# 1pcb.net
KiCad netlist of a schematic drawn in EAGLE
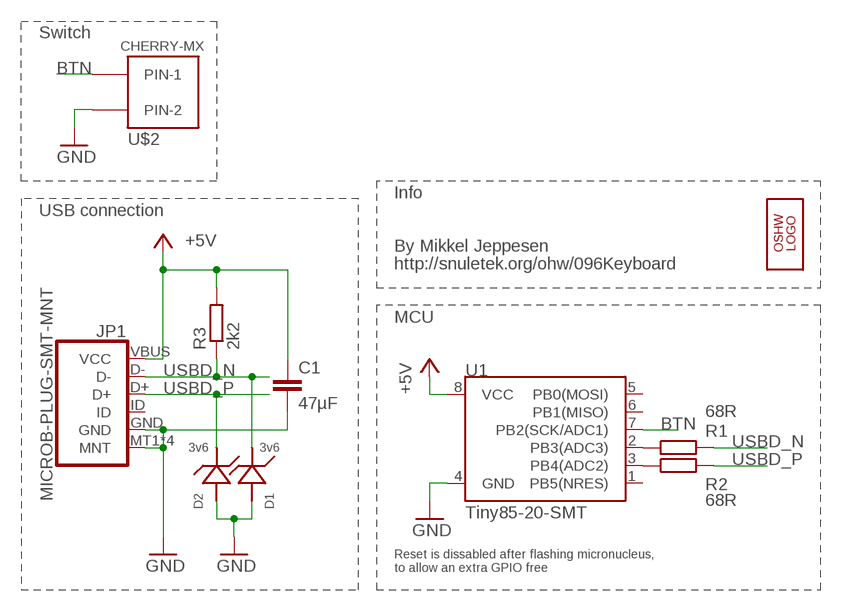
[diagram p0: schematic, sheet 1]

(export (version "E")
  (design (tool "Eeschema 10.0.6"))
  (components
    (comp (ref "C1")
      (value "47µF")
      (footprint "eagle-import:C3216")
      (libsource (lib "eagle-import") (part "C-EUC3216"))
    )
    (comp (ref "D1")
      (value "3v6")
      (footprint "eagle-import:SOD-523")
      (libsource (lib "eagle-import") (part "ZENER-DIODE"))
    )
    (comp (ref "D2")
      (value "3v6")
      (footprint "eagle-import:SOD-523")
      (libsource (lib "eagle-import") (part "ZENER-DIODE"))
    )
    (comp (ref "JP1")
      (value "MICROB-PLUG-SMT-MNT")
      (footprint "eagle-import:USB-MICROB")
      (libsource (lib "eagle-import") (part "MICROB-PLUG-SMT-MNT"))
    )
    (comp (ref "LOGO1")
      (value "OSHW_LOGO_6MILX0070-NT")
      (footprint "eagle-import:OSHW_6X70_NOTEXT")
      (libsource (lib "eagle-import") (part "OSHW_LOGO_6MILX0070-NT"))
    )
    (comp (ref "R1")
      (value "68R")
      (footprint "eagle-import:R0603")
      (libsource (lib "eagle-import") (part "R-EU_R0603"))
    )
    (comp (ref "R2")
      (value "68R")
      (footprint "eagle-import:R0603")
      (libsource (lib "eagle-import") (part "R-EU_R0603"))
    )
    (comp (ref "R3")
      (value "2k2")
      (footprint "eagle-import:R0603")
      (libsource (lib "eagle-import") (part "R-EU_R0603"))
    )
    (comp (ref "U$2")
      (value "CHERRY-MX-I")
      (footprint "eagle-import:CHERRY-MX-I")
      (libsource (lib "eagle-import") (part "CHERRY-MX-I"))
    )
    (comp (ref "U1")
      (value "Tiny85-20-SMT")
      (footprint "eagle-import:SO08-EIAJ")
      (libsource (lib "eagle-import") (part "ATTINY45TINY85-20-SMT"))
    )
  )
  (nets
    (net (code "1") (name "+5V") (class "Default")
      (node (ref "C1") (pin "1") (pinfunction "1_1") (pintype "passive"))
      (node (ref "JP1") (pin "VBUS") (pinfunction "VCC_VBUS") (pintype "bidirectional"))
      (node (ref "R3") (pin "2") (pinfunction "2_2") (pintype "passive"))
      (node (ref "U1") (pin "8") (pinfunction "VCC_8") (pintype "bidirectional"))
    )
    (net (code "2") (name "/BTN") (class "Default")
      (node (ref "U$2") (pin "PIN-1") (pinfunction "PIN-1_PIN-1") (pintype "bidirectional"))
      (node (ref "U1") (pin "7") (pinfunction "PB2(SCK/ADC1)_7") (pintype "bidirectional"))
    )
    (net (code "3") (name "/USBD_N") (class "Default")
      (node (ref "D1") (pin "C") (pinfunction "C_C") (pintype "bidirectional"))
      (node (ref "JP1") (pin "D-") (pinfunction "D-_D-") (pintype "bidirectional"))
      (node (ref "R1") (pin "2") (pinfunction "2_2") (pintype "passive"))
      (node (ref "R3") (pin "1") (pinfunction "1_1") (pintype "passive"))
    )
    (net (code "4") (name "/USBD_P") (class "Default")
      (node (ref "D2") (pin "C") (pinfunction "C_C") (pintype "bidirectional"))
      (node (ref "JP1") (pin "D+") (pinfunction "D+_D+") (pintype "bidirectional"))
      (node (ref "R2") (pin "2") (pinfunction "2_2") (pintype "passive"))
    )
    (net (code "5") (name "GND") (class "Default")
      (node (ref "C1") (pin "2") (pinfunction "2_2") (pintype "passive"))
      (node (ref "D1") (pin "A") (pinfunction "A_A") (pintype "bidirectional"))
      (node (ref "D2") (pin "A") (pinfunction "A_A") (pintype "bidirectional"))
      (node (ref "JP1") (pin "GND") (pinfunction "GND_GND") (pintype "bidirectional"))
      (node (ref "JP1") (pin "MT1") (pinfunction "MNT_MT1") (pintype "bidirectional"))
      (node (ref "JP1") (pin "MT2") (pinfunction "MNT_MT2") (pintype "bidirectional"))
      (node (ref "JP1") (pin "P$1") (pinfunction "MNT_P$1") (pintype "bidirectional"))
      (node (ref "JP1") (pin "P$2") (pinfunction "MNT_P$2") (pintype "bidirectional"))
      (node (ref "U$2") (pin "PIN-2") (pinfunction "PIN-2_PIN-2") (pintype "bidirectional"))
      (node (ref "U1") (pin "4") (pinfunction "GND_4") (pintype "bidirectional"))
    )
    (net (code "6") (name "Net-(U1-PB3(ADC3))") (class "Default")
      (node (ref "R1") (pin "1") (pinfunction "1_1") (pintype "passive"))
      (node (ref "U1") (pin "2") (pinfunction "PB3(ADC3)_2") (pintype "bidirectional"))
    )
    (net (code "7") (name "Net-(U1-PB4(ADC2))") (class "Default")
      (node (ref "R2") (pin "1") (pinfunction "1_1") (pintype "passive"))
      (node (ref "U1") (pin "3") (pinfunction "PB4(ADC2)_3") (pintype "bidirectional"))
    )
    (net (code "8") (name "unconnected-(JP1-PadID)") (class "Default")
      (node (ref "JP1") (pin "ID") (pinfunction "ID_ID") (pintype "bidirectional"))
    )
    (net (code "9") (name "unconnected-(U1-PB0(MOSI)-Pad5)") (class "Default")
      (node (ref "U1") (pin "5") (pinfunction "PB0(MOSI)_5") (pintype "bidirectional"))
    )
    (net (code "10") (name "unconnected-(U1-PB1(MISO)-Pad6)") (class "Default")
      (node (ref "U1") (pin "6") (pinfunction "PB1(MISO)_6") (pintype "bidirectional"))
    )
    (net (code "11") (name "unconnected-(U1-PB5(NRES)-Pad1)") (class "Default")
      (node (ref "U1") (pin "1") (pinfunction "PB5(NRES)_1") (pintype "bidirectional"))
    )
  )
)
